# ParallelCNC.net
KiCad netlist of a schematic drawn in EAGLE
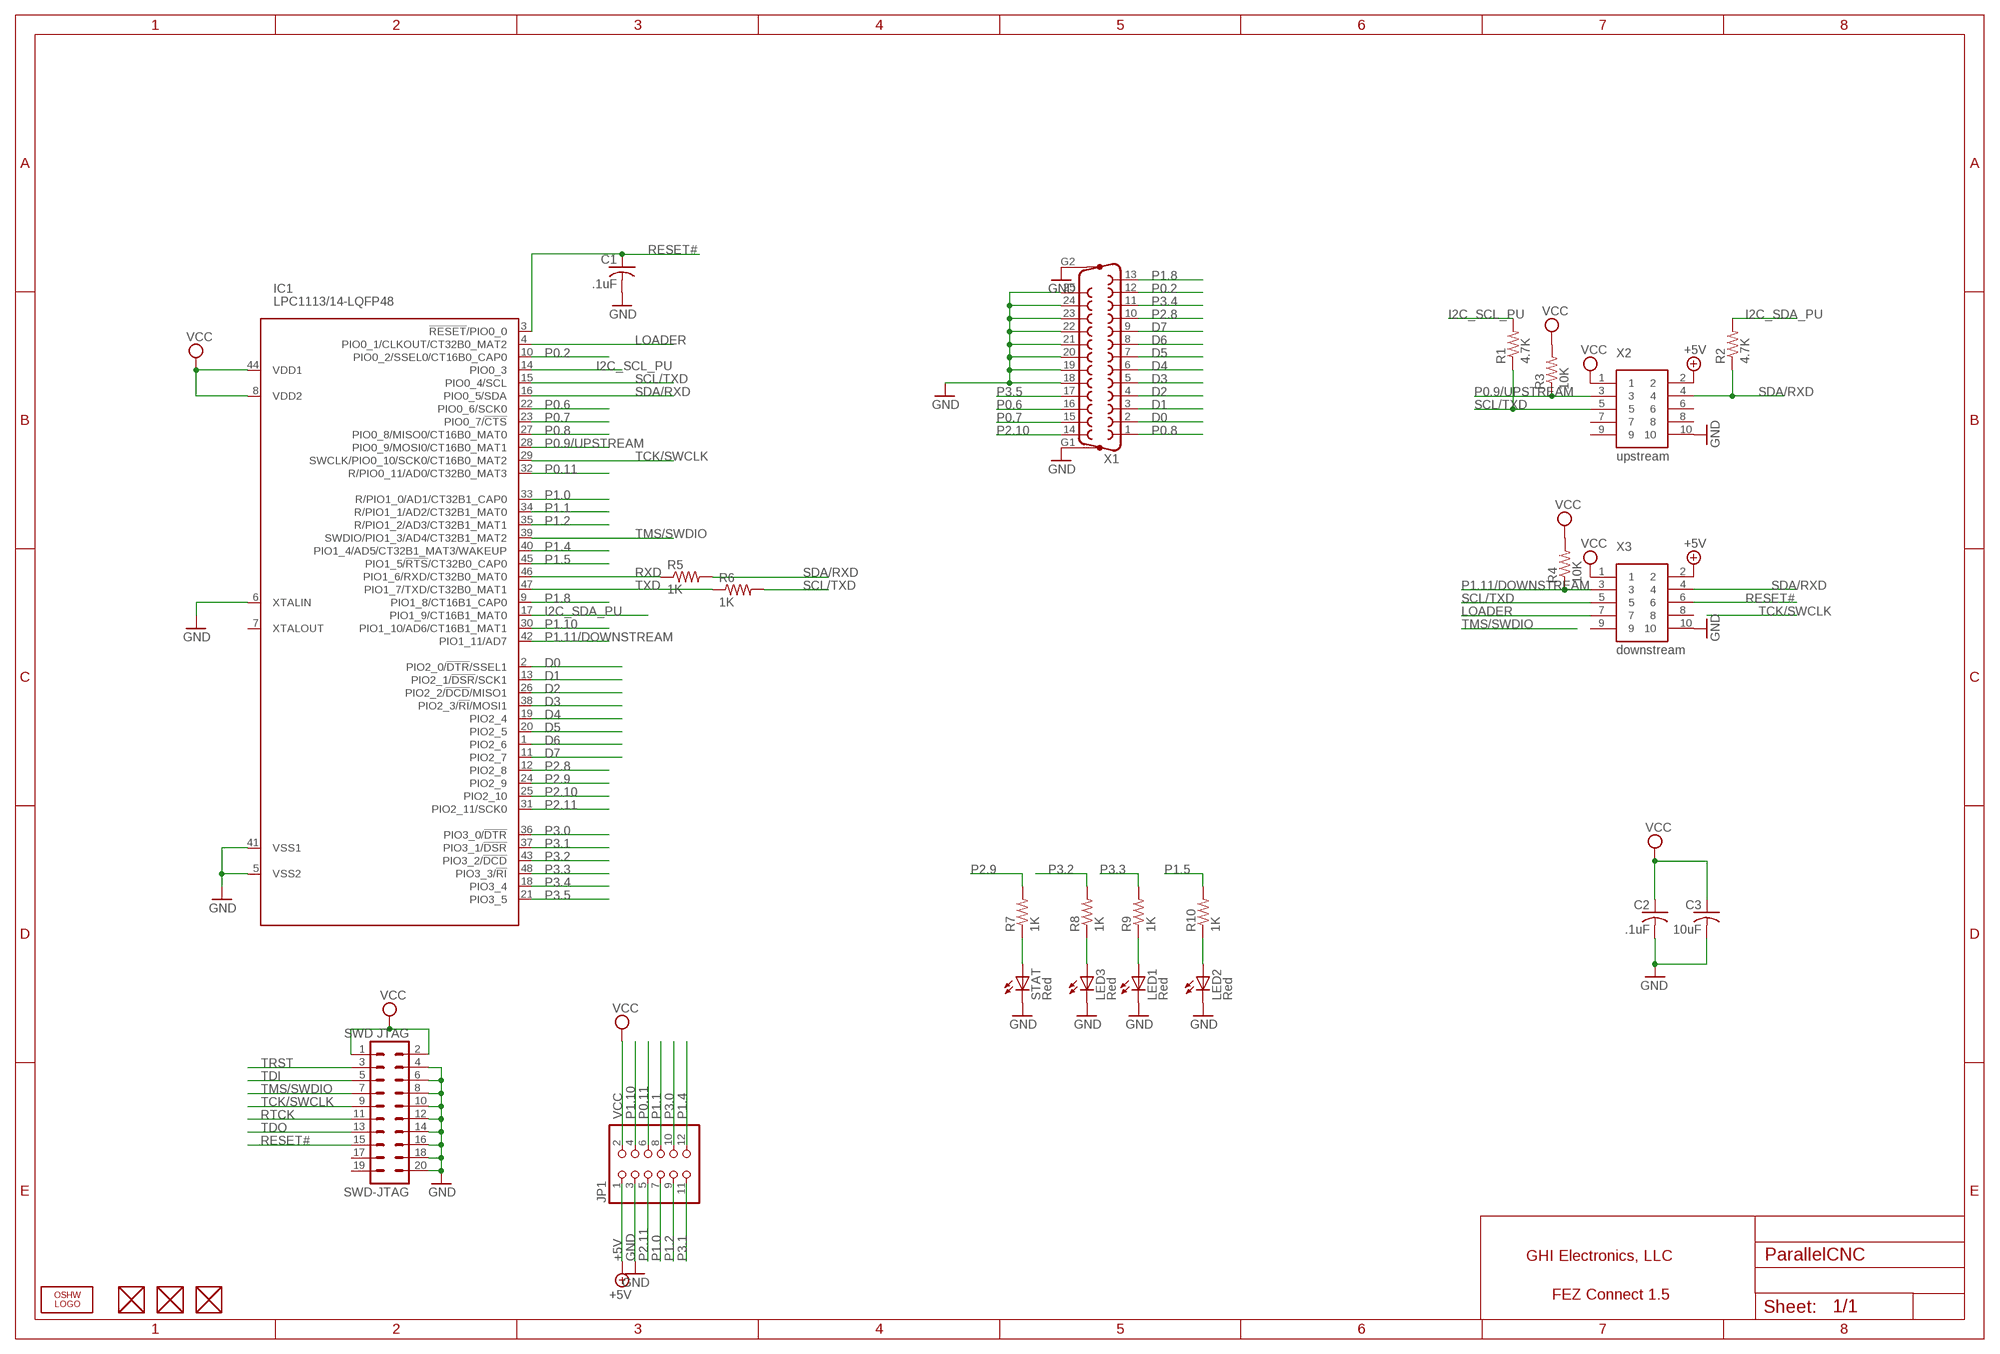
[diagram p0: schematic, sheet 1]

(export (version "E")
  (design (tool "Eeschema 10.0.6"))
  (components
    (comp (ref "C1")
      (value ".1uF")
      (footprint "eagle-import:C0603K")
      (libsource (lib "eagle-import") (part "C-USC0603K"))
    )
    (comp (ref "C2")
      (value ".1uF")
      (footprint "eagle-import:C0603K")
      (libsource (lib "eagle-import") (part "C-USC0603K"))
    )
    (comp (ref "C3")
      (value "10uF")
      (footprint "eagle-import:C0805K")
      (libsource (lib "eagle-import") (part "C-USC0805K"))
    )
    (comp (ref "FUD1")
      (value "FIDUCIAL")
      (footprint "eagle-import:FIDUCIAL_40MIL")
      (libsource (lib "eagle-import") (part "FIDUCIAL"))
    )
    (comp (ref "FUD2")
      (value "FIDUCIAL")
      (footprint "eagle-import:FIDUCIAL_40MIL")
      (libsource (lib "eagle-import") (part "FIDUCIAL"))
    )
    (comp (ref "FUD3")
      (value "FIDUCIAL")
      (footprint "eagle-import:FIDUCIAL_40MIL")
      (libsource (lib "eagle-import") (part "FIDUCIAL"))
    )
    (comp (ref "IC1")
      (value "LPC1113/14-LQFP48")
      (footprint "eagle-import:LQFP48")
      (libsource (lib "eagle-import") (part "LPC1113/14-LQFP48"))
    )
    (comp (ref "JP1")
      (value "PINHD-2X6")
      (footprint "eagle-import:2X06")
      (libsource (lib "eagle-import") (part "PINHD-2X6"))
    )
    (comp (ref "LED1")
      (value "Red")
      (footprint "eagle-import:CHIPLED_0805")
      (libsource (lib "eagle-import") (part "LEDCHIPLED_0805"))
    )
    (comp (ref "LED2")
      (value "Red")
      (footprint "eagle-import:CHIPLED_0805")
      (libsource (lib "eagle-import") (part "LEDCHIPLED_0805"))
    )
    (comp (ref "LED3")
      (value "Red")
      (footprint "eagle-import:CHIPLED_0805")
      (libsource (lib "eagle-import") (part "LEDCHIPLED_0805"))
    )
    (comp (ref "LOGO1")
      (value "LOGO-OSHW-FILLX0200-NT")
      (footprint "eagle-import:OSHW_FILLX200_NOTEXT")
      (libsource (lib "eagle-import") (part "LOGO-OSHW-FILLX0200-NT"))
    )
    (comp (ref "R1")
      (value "4.7K")
      (footprint "eagle-import:R0603")
      (libsource (lib "eagle-import") (part "R-US_R0603"))
    )
    (comp (ref "R2")
      (value "4.7K")
      (footprint "eagle-import:R0603")
      (libsource (lib "eagle-import") (part "R-US_R0603"))
    )
    (comp (ref "R3")
      (value "10K")
      (footprint "eagle-import:R0603")
      (libsource (lib "eagle-import") (part "R-US_R0603"))
    )
    (comp (ref "R4")
      (value "10K")
      (footprint "eagle-import:R0603")
      (libsource (lib "eagle-import") (part "R-US_R0603"))
    )
    (comp (ref "R5")
      (value "1K")
      (footprint "eagle-import:R0603")
      (libsource (lib "eagle-import") (part "R-US_R0603"))
    )
    (comp (ref "R6")
      (value "1K")
      (footprint "eagle-import:R0603")
      (libsource (lib "eagle-import") (part "R-US_R0603"))
    )
    (comp (ref "R7")
      (value "1K")
      (footprint "eagle-import:R0603")
      (libsource (lib "eagle-import") (part "R-US_R0603"))
    )
    (comp (ref "R8")
      (value "1K")
      (footprint "eagle-import:R0603")
      (libsource (lib "eagle-import") (part "R-US_R0603"))
    )
    (comp (ref "R9")
      (value "1K")
      (footprint "eagle-import:R0603")
      (libsource (lib "eagle-import") (part "R-US_R0603"))
    )
    (comp (ref "R10")
      (value "1K")
      (footprint "eagle-import:R0603")
      (libsource (lib "eagle-import") (part "R-US_R0603"))
    )
    (comp (ref "STAT")
      (value "Red")
      (footprint "eagle-import:CHIPLED_0805")
      (libsource (lib "eagle-import") (part "LEDCHIPLED_0805"))
    )
    (comp (ref "SWD-JTAG")
      (value "SWD JTAG")
      (footprint "eagle-import:MA10-2")
      (libsource (lib "eagle-import") (part "MA10-2"))
    )
    (comp (ref "X1")
      (value "F25HP")
      (footprint "eagle-import:F25HP")
      (libsource (lib "eagle-import") (part "F25HP"))
    )
    (comp (ref "X2")
      (value "upstream")
      (footprint "eagle-import:2X5_1.27MM")
      (libsource (lib "eagle-import") (part "2X5_1.27MM"))
    )
    (comp (ref "X3")
      (value "downstream")
      (footprint "eagle-import:2X5_1.27MM")
      (libsource (lib "eagle-import") (part "2X5_1.27MM"))
    )
  )
  (nets
    (net (code "1") (name "+5V") (class "Default")
      (node (ref "JP1") (pin "1") (pinfunction "1_1") (pintype "passive"))
      (node (ref "X2") (pin "2") (pinfunction "2_2") (pintype "bidirectional"))
      (node (ref "X3") (pin "2") (pinfunction "2_2") (pintype "bidirectional"))
    )
    (net (code "2") (name "/D0") (class "Default")
      (node (ref "IC1") (pin "2") (pinfunction "PIO2_0/~{DTR}/SSEL1_2") (pintype "bidirectional"))
      (node (ref "X1") (pin "2") (pinfunction "2_2") (pintype "passive"))
    )
    (net (code "3") (name "/D1") (class "Default")
      (node (ref "IC1") (pin "13") (pinfunction "PIO2_1/~{DSR}/SCK1_13") (pintype "bidirectional"))
      (node (ref "X1") (pin "3") (pinfunction "3_3") (pintype "passive"))
    )
    (net (code "4") (name "/D2") (class "Default")
      (node (ref "IC1") (pin "26") (pinfunction "PIO2_2/~{DCD}/MISO1_26") (pintype "bidirectional"))
      (node (ref "X1") (pin "4") (pinfunction "4_4") (pintype "passive"))
    )
    (net (code "5") (name "/D3") (class "Default")
      (node (ref "IC1") (pin "38") (pinfunction "PIO2_3/~{RI}/MOSI1_38") (pintype "bidirectional"))
      (node (ref "X1") (pin "5") (pinfunction "5_5") (pintype "passive"))
    )
    (net (code "6") (name "/D4") (class "Default")
      (node (ref "IC1") (pin "19") (pinfunction "PIO2_4_19") (pintype "bidirectional"))
      (node (ref "X1") (pin "6") (pinfunction "6_6") (pintype "passive"))
    )
    (net (code "7") (name "/D5") (class "Default")
      (node (ref "IC1") (pin "20") (pinfunction "PIO2_5_20") (pintype "bidirectional"))
      (node (ref "X1") (pin "7") (pinfunction "7_7") (pintype "passive"))
    )
    (net (code "8") (name "/D6") (class "Default")
      (node (ref "IC1") (pin "1") (pinfunction "PIO2_6_1") (pintype "bidirectional"))
      (node (ref "X1") (pin "8") (pinfunction "8_8") (pintype "passive"))
    )
    (net (code "9") (name "/D7") (class "Default")
      (node (ref "IC1") (pin "11") (pinfunction "PIO2_7_11") (pintype "bidirectional"))
      (node (ref "X1") (pin "9") (pinfunction "9_9") (pintype "passive"))
    )
    (net (code "10") (name "/I2C_SCL_PU") (class "Default")
      (node (ref "IC1") (pin "14") (pinfunction "PIO0_3_14") (pintype "bidirectional"))
      (node (ref "R1") (pin "2") (pinfunction "2_2") (pintype "passive"))
    )
    (net (code "11") (name "/I2C_SDA_PU") (class "Default")
      (node (ref "IC1") (pin "17") (pinfunction "PIO1_9/CT16B1_MAT0_17") (pintype "bidirectional"))
      (node (ref "R2") (pin "2") (pinfunction "2_2") (pintype "passive"))
    )
    (net (code "12") (name "/LOADER") (class "Default")
      (node (ref "IC1") (pin "4") (pinfunction "PIO0_1/CLKOUT/CT32B0_MAT2_4") (pintype "bidirectional"))
      (node (ref "X3") (pin "7") (pinfunction "7_7") (pintype "bidirectional"))
    )
    (net (code "13") (name "/P0.2") (class "Default")
      (node (ref "IC1") (pin "10") (pinfunction "PIO0_2/SSEL0/CT16B0_CAP0_10") (pintype "bidirectional"))
      (node (ref "X1") (pin "12") (pinfunction "12_12") (pintype "passive"))
    )
    (net (code "14") (name "/P0.6") (class "Default")
      (node (ref "IC1") (pin "22") (pinfunction "PIO0_6/SCK0_22") (pintype "bidirectional"))
      (node (ref "X1") (pin "16") (pinfunction "16_16") (pintype "passive"))
    )
    (net (code "15") (name "/P0.7") (class "Default")
      (node (ref "IC1") (pin "23") (pinfunction "PIO0_7/~{CTS}_23") (pintype "bidirectional"))
      (node (ref "X1") (pin "15") (pinfunction "15_15") (pintype "passive"))
    )
    (net (code "16") (name "/P0.8") (class "Default")
      (node (ref "IC1") (pin "27") (pinfunction "PIO0_8/MISO0/CT16B0_MAT0_27") (pintype "bidirectional"))
      (node (ref "X1") (pin "1") (pinfunction "1_1") (pintype "passive"))
    )
    (net (code "17") (name "/P0.9{slash}UPSTREAM") (class "Default")
      (node (ref "IC1") (pin "28") (pinfunction "PIO0_9/MOSI0/CT16B0_MAT1_28") (pintype "bidirectional"))
      (node (ref "R3") (pin "1") (pinfunction "1_1") (pintype "passive"))
      (node (ref "X2") (pin "3") (pinfunction "3_3") (pintype "bidirectional"))
    )
    (net (code "18") (name "/P0.11") (class "Default")
      (node (ref "IC1") (pin "32") (pinfunction "R/PIO0_11/AD0/CT32B0_MAT3_32") (pintype "bidirectional"))
      (node (ref "JP1") (pin "6") (pinfunction "6_6") (pintype "passive"))
    )
    (net (code "19") (name "/P1.0") (class "Default")
      (node (ref "IC1") (pin "33") (pinfunction "R/PIO1_0/AD1/CT32B1_CAP0_33") (pintype "bidirectional"))
      (node (ref "JP1") (pin "7") (pinfunction "7_7") (pintype "passive"))
    )
    (net (code "20") (name "/P1.1") (class "Default")
      (node (ref "IC1") (pin "34") (pinfunction "R/PIO1_1/AD2/CT32B1_MAT0_34") (pintype "bidirectional"))
      (node (ref "JP1") (pin "8") (pinfunction "8_8") (pintype "passive"))
    )
    (net (code "21") (name "/P1.2") (class "Default")
      (node (ref "IC1") (pin "35") (pinfunction "R/PIO1_2/AD3/CT32B1_MAT1_35") (pintype "bidirectional"))
      (node (ref "JP1") (pin "9") (pinfunction "9_9") (pintype "passive"))
    )
    (net (code "22") (name "/P1.4") (class "Default")
      (node (ref "IC1") (pin "40") (pinfunction "PIO1_4/AD5/CT32B1_MAT3/WAKEUP_40") (pintype "bidirectional"))
      (node (ref "JP1") (pin "12") (pinfunction "12_12") (pintype "passive"))
    )
    (net (code "23") (name "/P1.5") (class "Default")
      (node (ref "IC1") (pin "45") (pinfunction "PIO1_5/~{RTS}/CT32B0_CAP0_45") (pintype "bidirectional"))
      (node (ref "R10") (pin "2") (pinfunction "2_2") (pintype "passive"))
    )
    (net (code "24") (name "/P1.8") (class "Default")
      (node (ref "IC1") (pin "9") (pinfunction "PIO1_8/CT16B1_CAP0_9") (pintype "bidirectional"))
      (node (ref "X1") (pin "13") (pinfunction "13_13") (pintype "passive"))
    )
    (net (code "25") (name "/P1.10") (class "Default")
      (node (ref "IC1") (pin "30") (pinfunction "PIO1_10/AD6/CT16B1_MAT1_30") (pintype "bidirectional"))
      (node (ref "JP1") (pin "4") (pinfunction "4_4") (pintype "passive"))
    )
    (net (code "26") (name "/P1.11{slash}DOWNSTREAM") (class "Default")
      (node (ref "IC1") (pin "42") (pinfunction "PIO1_11/AD7_42") (pintype "bidirectional"))
      (node (ref "R4") (pin "1") (pinfunction "1_1") (pintype "passive"))
      (node (ref "X3") (pin "3") (pinfunction "3_3") (pintype "bidirectional"))
    )
    (net (code "27") (name "/P2.8") (class "Default")
      (node (ref "IC1") (pin "12") (pinfunction "PIO2_8_12") (pintype "bidirectional"))
      (node (ref "X1") (pin "10") (pinfunction "10_10") (pintype "passive"))
    )
    (net (code "28") (name "/P2.9") (class "Default")
      (node (ref "IC1") (pin "24") (pinfunction "PIO2_9_24") (pintype "bidirectional"))
      (node (ref "R7") (pin "2") (pinfunction "2_2") (pintype "passive"))
    )
    (net (code "29") (name "/P2.10") (class "Default")
      (node (ref "IC1") (pin "25") (pinfunction "PIO2_10_25") (pintype "bidirectional"))
      (node (ref "X1") (pin "14") (pinfunction "14_14") (pintype "passive"))
    )
    (net (code "30") (name "/P2.11") (class "Default")
      (node (ref "IC1") (pin "31") (pinfunction "PIO2_11/SCK0_31") (pintype "bidirectional"))
      (node (ref "JP1") (pin "5") (pinfunction "5_5") (pintype "passive"))
    )
    (net (code "31") (name "/P3.0") (class "Default")
      (node (ref "IC1") (pin "36") (pinfunction "PIO3_0/~{DTR}_36") (pintype "bidirectional"))
      (node (ref "JP1") (pin "10") (pinfunction "10_10") (pintype "passive"))
    )
    (net (code "32") (name "/P3.1") (class "Default")
      (node (ref "IC1") (pin "37") (pinfunction "PIO3_1/~{DSR}_37") (pintype "bidirectional"))
      (node (ref "JP1") (pin "11") (pinfunction "11_11") (pintype "passive"))
    )
    (net (code "33") (name "/P3.2") (class "Default")
      (node (ref "IC1") (pin "43") (pinfunction "PIO3_2/~{DCD}_43") (pintype "bidirectional"))
      (node (ref "R8") (pin "2") (pinfunction "2_2") (pintype "passive"))
    )
    (net (code "34") (name "/P3.3") (class "Default")
      (node (ref "IC1") (pin "48") (pinfunction "PIO3_3/~{RI}_48") (pintype "bidirectional"))
      (node (ref "R9") (pin "2") (pinfunction "2_2") (pintype "passive"))
    )
    (net (code "35") (name "/P3.4") (class "Default")
      (node (ref "IC1") (pin "18") (pinfunction "PIO3_4_18") (pintype "bidirectional"))
      (node (ref "X1") (pin "11") (pinfunction "11_11") (pintype "passive"))
    )
    (net (code "36") (name "/P3.5") (class "Default")
      (node (ref "IC1") (pin "21") (pinfunction "PIO3_5_21") (pintype "bidirectional"))
      (node (ref "X1") (pin "17") (pinfunction "17_17") (pintype "passive"))
    )
    (net (code "37") (name "/RESET#") (class "Default")
      (node (ref "C1") (pin "1") (pinfunction "1_1") (pintype "passive"))
      (node (ref "IC1") (pin "3") (pinfunction "~{RESET}/PIO0_0_3") (pintype "bidirectional"))
      (node (ref "SWD-JTAG") (pin "15") (pinfunction "15_15") (pintype "passive"))
      (node (ref "X3") (pin "6") (pinfunction "6_6") (pintype "bidirectional"))
    )
    (net (code "38") (name "/RTCK") (class "Default")
      (node (ref "SWD-JTAG") (pin "11") (pinfunction "11_11") (pintype "passive"))
    )
    (net (code "39") (name "/RXD") (class "Default")
      (node (ref "IC1") (pin "46") (pinfunction "PIO1_6/RXD/CT32B0_MAT0_46") (pintype "bidirectional"))
      (node (ref "R5") (pin "1") (pinfunction "1_1") (pintype "passive"))
    )
    (net (code "40") (name "/SCL{slash}TXD") (class "Default")
      (node (ref "IC1") (pin "15") (pinfunction "PIO0_4/SCL_15") (pintype "bidirectional"))
      (node (ref "R1") (pin "1") (pinfunction "1_1") (pintype "passive"))
      (node (ref "R6") (pin "2") (pinfunction "2_2") (pintype "passive"))
      (node (ref "X2") (pin "5") (pinfunction "5_5") (pintype "bidirectional"))
      (node (ref "X3") (pin "5") (pinfunction "5_5") (pintype "bidirectional"))
    )
    (net (code "41") (name "/SDA{slash}RXD") (class "Default")
      (node (ref "IC1") (pin "16") (pinfunction "PIO0_5/SDA_16") (pintype "bidirectional"))
      (node (ref "R2") (pin "1") (pinfunction "1_1") (pintype "passive"))
      (node (ref "R5") (pin "2") (pinfunction "2_2") (pintype "passive"))
      (node (ref "X2") (pin "4") (pinfunction "4_4") (pintype "bidirectional"))
      (node (ref "X3") (pin "4") (pinfunction "4_4") (pintype "bidirectional"))
    )
    (net (code "42") (name "/TCK{slash}SWCLK") (class "Default")
      (node (ref "IC1") (pin "29") (pinfunction "SWCLK/PIO0_10/SCK0/CT16B0_MAT2_29") (pintype "bidirectional"))
      (node (ref "SWD-JTAG") (pin "9") (pinfunction "9_9") (pintype "passive"))
    )
    (net (code "43") (name "/TDI") (class "Default")
      (node (ref "SWD-JTAG") (pin "5") (pinfunction "5_5") (pintype "passive"))
    )
    (net (code "44") (name "/TDO") (class "Default")
      (node (ref "SWD-JTAG") (pin "13") (pinfunction "13_13") (pintype "passive"))
    )
    (net (code "45") (name "/TMS{slash}SWDIO") (class "Default")
      (node (ref "IC1") (pin "39") (pinfunction "SWDIO/PIO1_3/AD4/CT32B1_MAT2_39") (pintype "bidirectional"))
      (node (ref "SWD-JTAG") (pin "7") (pinfunction "7_7") (pintype "passive"))
    )
    (net (code "46") (name "/TRST") (class "Default")
      (node (ref "SWD-JTAG") (pin "3") (pinfunction "3_3") (pintype "passive"))
    )
    (net (code "47") (name "/TXD") (class "Default")
      (node (ref "IC1") (pin "47") (pinfunction "PIO1_7/TXD/CT32B0_MAT1_47") (pintype "bidirectional"))
      (node (ref "R6") (pin "1") (pinfunction "1_1") (pintype "passive"))
    )
    (net (code "48") (name "GND") (class "Default")
      (node (ref "C1") (pin "2") (pinfunction "2_2") (pintype "passive"))
      (node (ref "C2") (pin "2") (pinfunction "2_2") (pintype "passive"))
      (node (ref "C3") (pin "2") (pinfunction "2_2") (pintype "passive"))
      (node (ref "IC1") (pin "41") (pinfunction "VSS1_41") (pintype "power_in"))
      (node (ref "IC1") (pin "5") (pinfunction "VSS2_5") (pintype "power_in"))
      (node (ref "IC1") (pin "6") (pinfunction "XTALIN_6") (pintype "passive"))
      (node (ref "JP1") (pin "3") (pinfunction "3_3") (pintype "passive"))
      (node (ref "LED1") (pin "C") (pinfunction "C_C") (pintype "passive"))
      (node (ref "LED2") (pin "C") (pinfunction "C_C") (pintype "passive"))
      (node (ref "LED3") (pin "C") (pinfunction "C_C") (pintype "passive"))
      (node (ref "STAT") (pin "C") (pinfunction "C_C") (pintype "passive"))
      (node (ref "SWD-JTAG") (pin "10") (pinfunction "10_10") (pintype "passive"))
      (node (ref "SWD-JTAG") (pin "12") (pinfunction "12_12") (pintype "passive"))
      (node (ref "SWD-JTAG") (pin "14") (pinfunction "14_14") (pintype "passive"))
      (node (ref "SWD-JTAG") (pin "16") (pinfunction "16_16") (pintype "passive"))
      (node (ref "SWD-JTAG") (pin "18") (pinfunction "18_18") (pintype "passive"))
      (node (ref "SWD-JTAG") (pin "20") (pinfunction "20_20") (pintype "passive"))
      (node (ref "SWD-JTAG") (pin "4") (pinfunction "4_4") (pintype "passive"))
      (node (ref "SWD-JTAG") (pin "6") (pinfunction "6_6") (pintype "passive"))
      (node (ref "SWD-JTAG") (pin "8") (pinfunction "8_8") (pintype "passive"))
      (node (ref "X1") (pin "18") (pinfunction "18_18") (pintype "passive"))
      (node (ref "X1") (pin "19") (pinfunction "19_19") (pintype "passive"))
      (node (ref "X1") (pin "20") (pinfunction "20_20") (pintype "passive"))
      (node (ref "X1") (pin "21") (pinfunction "21_21") (pintype "passive"))
      (node (ref "X1") (pin "22") (pinfunction "22_22") (pintype "passive"))
      (node (ref "X1") (pin "23") (pinfunction "23_23") (pintype "passive"))
      (node (ref "X1") (pin "24") (pinfunction "24_24") (pintype "passive"))
      (node (ref "X1") (pin "25") (pinfunction "25_25") (pintype "passive"))
      (node (ref "X1") (pin "G1") (pinfunction "G1_G1") (pintype "passive"))
      (node (ref "X1") (pin "G2") (pinfunction "G2_G2") (pintype "passive"))
      (node (ref "X2") (pin "10") (pinfunction "10_10") (pintype "bidirectional"))
      (node (ref "X3") (pin "10") (pinfunction "10_10") (pintype "bidirectional"))
    )
    (net (code "49") (name "Net-(LED1-PadA)") (class "Default")
      (node (ref "LED1") (pin "A") (pinfunction "A_A") (pintype "passive"))
      (node (ref "R9") (pin "1") (pinfunction "1_1") (pintype "passive"))
    )
    (net (code "50") (name "Net-(LED2-PadA)") (class "Default")
      (node (ref "LED2") (pin "A") (pinfunction "A_A") (pintype "passive"))
      (node (ref "R10") (pin "1") (pinfunction "1_1") (pintype "passive"))
    )
    (net (code "51") (name "Net-(LED3-PadA)") (class "Default")
      (node (ref "LED3") (pin "A") (pinfunction "A_A") (pintype "passive"))
      (node (ref "R8") (pin "1") (pinfunction "1_1") (pintype "passive"))
    )
    (net (code "52") (name "Net-(R7-Pad1)") (class "Default")
      (node (ref "R7") (pin "1") (pinfunction "1_1") (pintype "passive"))
      (node (ref "STAT") (pin "A") (pinfunction "A_A") (pintype "passive"))
    )
    (net (code "53") (name "VCC") (class "Default")
      (node (ref "C2") (pin "1") (pinfunction "1_1") (pintype "passive"))
      (node (ref "C3") (pin "1") (pinfunction "1_1") (pintype "passive"))
      (node (ref "IC1") (pin "44") (pinfunction "VDD1_44") (pintype "power_in"))
      (node (ref "IC1") (pin "8") (pinfunction "VDD2_8") (pintype "power_in"))
      (node (ref "JP1") (pin "2") (pinfunction "2_2") (pintype "passive"))
      (node (ref "R3") (pin "2") (pinfunction "2_2") (pintype "passive"))
      (node (ref "R4") (pin "2") (pinfunction "2_2") (pintype "passive"))
      (node (ref "SWD-JTAG") (pin "1") (pinfunction "1_1") (pintype "passive"))
      (node (ref "SWD-JTAG") (pin "2") (pinfunction "2_2") (pintype "passive"))
      (node (ref "X2") (pin "1") (pinfunction "1_1") (pintype "bidirectional"))
      (node (ref "X3") (pin "1") (pinfunction "1_1") (pintype "bidirectional"))
    )
    (net (code "54") (name "unconnected-(FUD1-PadP$1)") (class "Default")
      (node (ref "FUD1") (pin "P$1") (pinfunction "P$1_P$1") (pintype "no_connect"))
    )
    (net (code "55") (name "unconnected-(FUD2-PadP$1)") (class "Default")
      (node (ref "FUD2") (pin "P$1") (pinfunction "P$1_P$1") (pintype "no_connect"))
    )
    (net (code "56") (name "unconnected-(FUD3-PadP$1)") (class "Default")
      (node (ref "FUD3") (pin "P$1") (pinfunction "P$1_P$1") (pintype "no_connect"))
    )
    (net (code "57") (name "unconnected-(IC1-XTALOUT-Pad7)") (class "Default")
      (node (ref "IC1") (pin "7") (pinfunction "XTALOUT_7") (pintype "passive"))
    )
    (net (code "58") (name "unconnected-(SWD-JTAG-Pad17)") (class "Default")
      (node (ref "SWD-JTAG") (pin "17") (pinfunction "17_17") (pintype "passive"))
    )
    (net (code "59") (name "unconnected-(SWD-JTAG-Pad19)") (class "Default")
      (node (ref "SWD-JTAG") (pin "19") (pinfunction "19_19") (pintype "passive"))
    )
    (net (code "60") (name "unconnected-(X2-Pad6)") (class "Default")
      (node (ref "X2") (pin "6") (pinfunction "6_6") (pintype "bidirectional"))
    )
    (net (code "61") (name "unconnected-(X2-Pad7)") (class "Default")
      (node (ref "X2") (pin "7") (pinfunction "7_7") (pintype "bidirectional"))
    )
    (net (code "62") (name "unconnected-(X2-Pad8)") (class "Default")
      (node (ref "X2") (pin "8") (pinfunction "8_8") (pintype "bidirectional"))
    )
    (net (code "63") (name "unconnected-(X2-Pad9)") (class "Default")
      (node (ref "X2") (pin "9") (pinfunction "9_9") (pintype "bidirectional"))
    )
    (net (code "64") (name "unconnected-(X3-Pad8)") (class "Default")
      (node (ref "X3") (pin "8") (pinfunction "8_8") (pintype "bidirectional"))
    )
    (net (code "65") (name "unconnected-(X3-Pad9)") (class "Default")
      (node (ref "X3") (pin "9") (pinfunction "9_9") (pintype "bidirectional"))
    )
  )
)
